# ButtonLedBoard.net
KiCad netlist of a schematic drawn in EAGLE
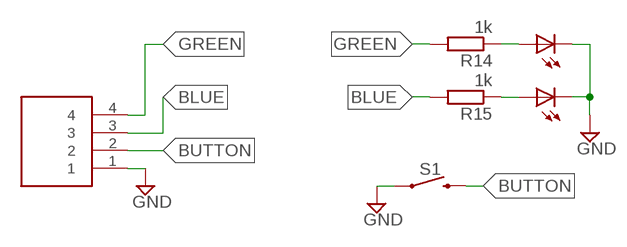
[diagram p0: schematic, sheet 1]

(export (version "E")
  (design (tool "Eeschema 10.0.6"))
  (components
    (comp (ref "J1")
      (value "826629-4")
      (footprint "eagle-import:TE_826629-4")
      (fields (field (name "MF") "TE Connectivity"))
      (libsource (lib "eagle-import") (part "826629-4"))
    )
    (comp (ref "LED1")
      (value "LEDCHIP-LED0603")
      (footprint "eagle-import:CHIP-LED0603")
      (libsource (lib "eagle-import") (part "LEDCHIP-LED0603"))
    )
    (comp (ref "LED2")
      (value "LEDCHIP-LED0603")
      (footprint "eagle-import:CHIP-LED0603")
      (libsource (lib "eagle-import") (part "LEDCHIP-LED0603"))
    )
    (comp (ref "R14")
      (value "1k")
      (footprint "eagle-import:R0603")
      (libsource (lib "eagle-import") (part "R-EU_R0603"))
    )
    (comp (ref "R15")
      (value "1k")
      (footprint "eagle-import:R0603")
      (libsource (lib "eagle-import") (part "R-EU_R0603"))
    )
    (comp (ref "S1")
      (value "MOMENTARY-SWITCH-SPST-SMD-6.0X3.5MM")
      (footprint "eagle-import:TACTILE_SWITCH_SMD_6.0X3.5MM")
      (libsource (lib "eagle-import") (part "MOMENTARY-SWITCH-SPST-SMD-6.0X3.5MM"))
    )
  )
  (nets
    (net (code "1") (name "BLUE") (class "Default")
      (node (ref "J1") (pin "3") (pinfunction "3_3") (pintype "passive"))
      (node (ref "R15") (pin "2") (pinfunction "2_2") (pintype "passive"))
    )
    (net (code "2") (name "BUTTON") (class "Default")
      (node (ref "J1") (pin "2") (pinfunction "2_2") (pintype "passive"))
      (node (ref "S1") (pin "2") (pinfunction "2_2") (pintype "passive"))
    )
    (net (code "3") (name "GND") (class "Default")
      (node (ref "J1") (pin "1") (pinfunction "1_1") (pintype "passive"))
      (node (ref "LED1") (pin "C") (pinfunction "C_C") (pintype "passive"))
      (node (ref "LED2") (pin "C") (pinfunction "C_C") (pintype "passive"))
      (node (ref "S1") (pin "1") (pinfunction "1_1") (pintype "passive"))
    )
    (net (code "4") (name "GREEN") (class "Default")
      (node (ref "J1") (pin "4") (pinfunction "4_4") (pintype "passive"))
      (node (ref "R14") (pin "2") (pinfunction "2_2") (pintype "passive"))
    )
    (net (code "5") (name "Net-(LED1-PadA)") (class "Default")
      (node (ref "LED1") (pin "A") (pinfunction "A_A") (pintype "passive"))
      (node (ref "R14") (pin "1") (pinfunction "1_1") (pintype "passive"))
    )
    (net (code "6") (name "Net-(LED2-PadA)") (class "Default")
      (node (ref "LED2") (pin "A") (pinfunction "A_A") (pintype "passive"))
      (node (ref "R15") (pin "1") (pinfunction "1_1") (pintype "passive"))
    )
  )
)
